# Top.net
KiCad netlist of a schematic drawn in Altium Designer
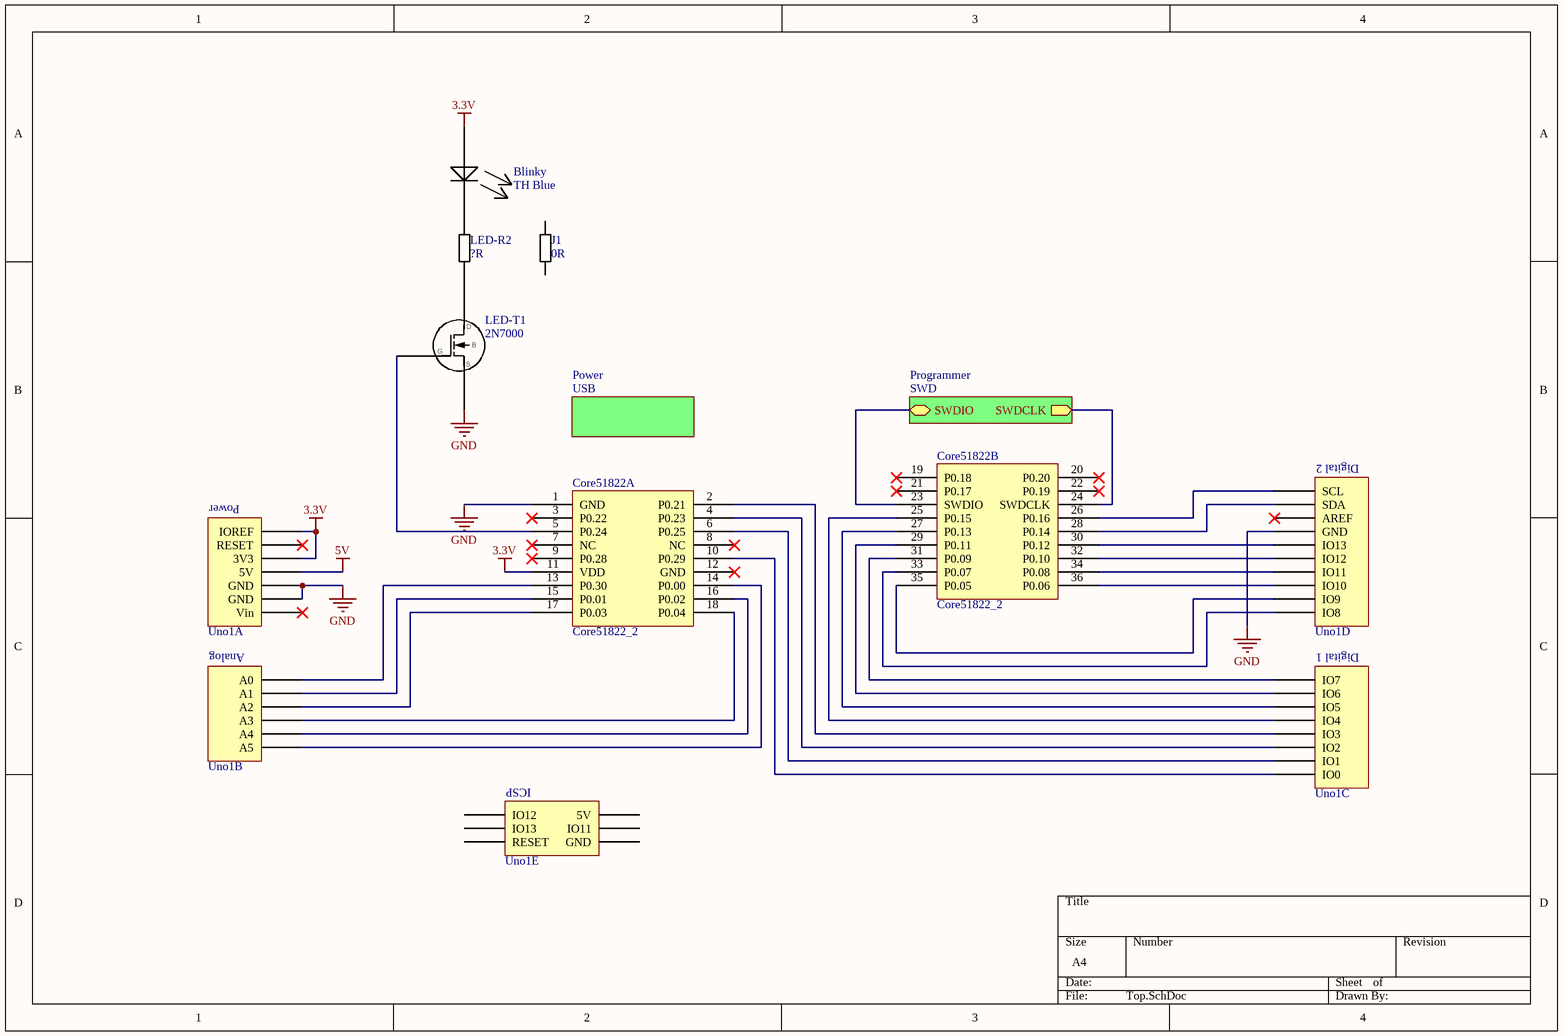
[diagram p0: Top.SchDoc]

(export (version "E")
  (design (tool "Eeschema 10.0.6"))
  (components
    (comp (ref "Blinky") (value "TH Blue") (footprint "LED 3mm") (libsource (lib "LEDs") (part "LED")))
    (comp (ref "Core51822")
      (value "Core51822_2")
      (footprint "Core51822")
      (libsource (lib "Modules") (part "Core51822_2"))
    )
    (comp (ref "J1")
      (value "0R")
      (footprint "R 0805 / 2012 wide")
      (libsource (lib "Standard") (part "Resistor"))
    )
    (comp (ref "LED-R2")
      (value "?R")
      (footprint "R 0805 / 2012")
      (libsource (lib "Standard") (part "Resistor"))
    )
    (comp (ref "LED-T1")
      (value "2N7000")
      (footprint "SOT-23-3")
      (description "N-FET")
      (libsource (lib "ICs") (part "2N7000"))
    )
    (comp (ref "Uno1")
      (value "Arduino Uno")
      (footprint "Arduino Uno Adapter")
      (libsource (lib "Arduino") (part "Arduino Uno"))
    )
  )
  (nets
    (net (code "1") (name "/SWDCLK") (class "Default")
      (node (ref "Core51822") (pin "24") (pinfunction "SWDCLK_24") (pintype "passive"))
    )
    (net (code "2") (name "/SWDIO") (class "Default")
      (node (ref "Core51822") (pin "23") (pinfunction "SWDIO_23") (pintype "passive"))
    )
    (net (code "3") (name "3.3V") (class "Default")
      (node (ref "Blinky") (pin "1") (pinfunction "+_1") (pintype "passive"))
      (node (ref "Core51822") (pin "11") (pinfunction "VDD_11") (pintype "passive"))
      (node (ref "Uno1") (pin "3V3") (pinfunction "3V3_3V3") (pintype "passive"))
      (node (ref "Uno1") (pin "IOREF") (pinfunction "IOREF_IOREF") (pintype "passive"))
    )
    (net (code "4") (name "5V") (class "Default")
      (node (ref "Uno1") (pin "5V") (pinfunction "5V_5V") (pintype "passive"))
    )
    (net (code "5") (name "GND") (class "Default")
      (node (ref "Core51822") (pin "1") (pinfunction "GND_1") (pintype "passive"))
      (node (ref "LED-T1") (pin "2") (pinfunction "2_2") (pintype "passive"))
      (node (ref "Uno1") (pin "GND1") (pinfunction "GND_GND1") (pintype "passive"))
      (node (ref "Uno1") (pin "GND2") (pinfunction "GND_GND2") (pintype "passive"))
      (node (ref "Uno1") (pin "GND3") (pinfunction "GND_GND3") (pintype "passive"))
    )
    (net (code "6") (name "Net-(Blinky--)") (class "Default")
      (node (ref "Blinky") (pin "2") (pinfunction "-_2") (pintype "passive"))
      (node (ref "LED-R2") (pin "2") (pinfunction "2_2") (pintype "passive"))
    )
    (net (code "7") (name "Net-(Core51822A-P0.00)") (class "Default")
      (node (ref "Core51822") (pin "14") (pinfunction "P0.00_14") (pintype "passive"))
      (node (ref "Uno1") (pin "A5") (pinfunction "A5_A5") (pintype "passive"))
    )
    (net (code "8") (name "Net-(Core51822A-P0.01)") (class "Default")
      (node (ref "Core51822") (pin "15") (pinfunction "P0.01_15") (pintype "passive"))
      (node (ref "Uno1") (pin "A1") (pinfunction "A1_A1") (pintype "passive"))
    )
    (net (code "9") (name "Net-(Core51822A-P0.02)") (class "Default")
      (node (ref "Core51822") (pin "16") (pinfunction "P0.02_16") (pintype "passive"))
      (node (ref "Uno1") (pin "A4") (pinfunction "A4_A4") (pintype "passive"))
    )
    (net (code "10") (name "Net-(Core51822A-P0.03)") (class "Default")
      (node (ref "Core51822") (pin "17") (pinfunction "P0.03_17") (pintype "passive"))
      (node (ref "Uno1") (pin "A2") (pinfunction "A2_A2") (pintype "passive"))
    )
    (net (code "11") (name "Net-(Core51822A-P0.04)") (class "Default")
      (node (ref "Core51822") (pin "18") (pinfunction "P0.04_18") (pintype "passive"))
      (node (ref "Uno1") (pin "A3") (pinfunction "A3_A3") (pintype "passive"))
    )
    (net (code "12") (name "Net-(Core51822A-P0.21)") (class "Default")
      (node (ref "Core51822") (pin "2") (pinfunction "P0.21_2") (pintype "passive"))
      (node (ref "Uno1") (pin "3") (pinfunction "IO3_3") (pintype "passive"))
    )
    (net (code "13") (name "Net-(Core51822A-P0.23)") (class "Default")
      (node (ref "Core51822") (pin "4") (pinfunction "P0.23_4") (pintype "passive"))
      (node (ref "Uno1") (pin "2") (pinfunction "IO2_2") (pintype "passive"))
    )
    (net (code "14") (name "Net-(Core51822A-P0.24)") (class "Default")
      (node (ref "Core51822") (pin "5") (pinfunction "P0.24_5") (pintype "passive"))
      (node (ref "LED-T1") (pin "1") (pinfunction "1_1") (pintype "passive"))
    )
    (net (code "15") (name "Net-(Core51822A-P0.25)") (class "Default")
      (node (ref "Core51822") (pin "6") (pinfunction "P0.25_6") (pintype "passive"))
      (node (ref "Uno1") (pin "1") (pinfunction "IO1_1") (pintype "passive"))
    )
    (net (code "16") (name "Net-(Core51822A-P0.29)") (class "Default")
      (node (ref "Core51822") (pin "10") (pinfunction "P0.29_10") (pintype "passive"))
      (node (ref "Uno1") (pin "0") (pinfunction "IO0_0") (pintype "passive"))
    )
    (net (code "17") (name "Net-(Core51822A-P0.30)") (class "Default")
      (node (ref "Core51822") (pin "13") (pinfunction "P0.30_13") (pintype "passive"))
      (node (ref "Uno1") (pin "A0") (pinfunction "A0_A0") (pintype "passive"))
    )
    (net (code "18") (name "Net-(Core51822B-P0.05)") (class "Default")
      (node (ref "Core51822") (pin "35") (pinfunction "P0.05_35") (pintype "passive"))
      (node (ref "Uno1") (pin "9") (pinfunction "IO9_9") (pintype "passive"))
    )
    (net (code "19") (name "Net-(Core51822B-P0.06)") (class "Default")
      (node (ref "Core51822") (pin "36") (pinfunction "P0.06_36") (pintype "passive"))
      (node (ref "Uno1") (pin "10") (pinfunction "IO10_10") (pintype "passive"))
    )
    (net (code "20") (name "Net-(Core51822B-P0.07)") (class "Default")
      (node (ref "Core51822") (pin "33") (pinfunction "P0.07_33") (pintype "passive"))
      (node (ref "Uno1") (pin "8") (pinfunction "IO8_8") (pintype "passive"))
    )
    (net (code "21") (name "Net-(Core51822B-P0.08)") (class "Default")
      (node (ref "Core51822") (pin "34") (pinfunction "P0.08_34") (pintype "passive"))
      (node (ref "Uno1") (pin "11") (pinfunction "IO11_11") (pintype "passive"))
    )
    (net (code "22") (name "Net-(Core51822B-P0.09)") (class "Default")
      (node (ref "Core51822") (pin "31") (pinfunction "P0.09_31") (pintype "passive"))
      (node (ref "Uno1") (pin "7") (pinfunction "IO7_7") (pintype "passive"))
    )
    (net (code "23") (name "Net-(Core51822B-P0.10)") (class "Default")
      (node (ref "Core51822") (pin "32") (pinfunction "P0.10_32") (pintype "passive"))
      (node (ref "Uno1") (pin "12") (pinfunction "IO12_12") (pintype "passive"))
    )
    (net (code "24") (name "Net-(Core51822B-P0.11)") (class "Default")
      (node (ref "Core51822") (pin "29") (pinfunction "P0.11_29") (pintype "passive"))
      (node (ref "Uno1") (pin "6") (pinfunction "IO6_6") (pintype "passive"))
    )
    (net (code "25") (name "Net-(Core51822B-P0.12)") (class "Default")
      (node (ref "Core51822") (pin "30") (pinfunction "P0.12_30") (pintype "passive"))
      (node (ref "Uno1") (pin "13") (pinfunction "IO13_13") (pintype "passive"))
    )
    (net (code "26") (name "Net-(Core51822B-P0.13)") (class "Default")
      (node (ref "Core51822") (pin "27") (pinfunction "P0.13_27") (pintype "passive"))
      (node (ref "Uno1") (pin "5") (pinfunction "IO5_5") (pintype "passive"))
    )
    (net (code "27") (name "Net-(Core51822B-P0.14)") (class "Default")
      (node (ref "Core51822") (pin "28") (pinfunction "P0.14_28") (pintype "passive"))
      (node (ref "Uno1") (pin "SDA") (pinfunction "SDA_SDA") (pintype "passive"))
    )
    (net (code "28") (name "Net-(Core51822B-P0.15)") (class "Default")
      (node (ref "Core51822") (pin "25") (pinfunction "P0.15_25") (pintype "passive"))
      (node (ref "Uno1") (pin "4") (pinfunction "IO4_4") (pintype "passive"))
    )
    (net (code "29") (name "Net-(Core51822B-P0.16)") (class "Default")
      (node (ref "Core51822") (pin "26") (pinfunction "P0.16_26") (pintype "passive"))
      (node (ref "Uno1") (pin "SCL") (pinfunction "SCL_SCL") (pintype "passive"))
    )
    (net (code "30") (name "Net-(LED-R2-Pad1)") (class "Default")
      (node (ref "LED-R2") (pin "1") (pinfunction "1_1") (pintype "passive"))
      (node (ref "LED-T1") (pin "3") (pinfunction "3_3") (pintype "passive"))
    )
    (net (code "31") (name "unconnected-(Core51822A-GND-Pad12)") (class "Default")
      (node (ref "Core51822") (pin "12") (pinfunction "GND_12") (pintype "passive+no_connect"))
    )
    (net (code "32") (name "unconnected-(Core51822A-NC-Pad7)") (class "Default")
      (node (ref "Core51822") (pin "7") (pinfunction "NC_7") (pintype "passive+no_connect"))
    )
    (net (code "33") (name "unconnected-(Core51822A-NC-Pad8)") (class "Default")
      (node (ref "Core51822") (pin "8") (pinfunction "NC_8") (pintype "passive+no_connect"))
    )
    (net (code "34") (name "unconnected-(Core51822A-P0.22-Pad3)") (class "Default")
      (node (ref "Core51822") (pin "3") (pinfunction "P0.22_3") (pintype "passive+no_connect"))
    )
    (net (code "35") (name "unconnected-(Core51822A-P0.28-Pad9)") (class "Default")
      (node (ref "Core51822") (pin "9") (pinfunction "P0.28_9") (pintype "passive+no_connect"))
    )
    (net (code "36") (name "unconnected-(Core51822B-P0.17-Pad21)") (class "Default")
      (node (ref "Core51822") (pin "21") (pinfunction "P0.17_21") (pintype "power_in+no_connect"))
    )
    (net (code "37") (name "unconnected-(Core51822B-P0.18-Pad19)") (class "Default")
      (node (ref "Core51822") (pin "19") (pinfunction "P0.18_19") (pintype "passive+no_connect"))
    )
    (net (code "38") (name "unconnected-(Core51822B-P0.19-Pad22)") (class "Default")
      (node (ref "Core51822") (pin "22") (pinfunction "P0.19_22") (pintype "passive+no_connect"))
    )
    (net (code "39") (name "unconnected-(Core51822B-P0.20-Pad20)") (class "Default")
      (node (ref "Core51822") (pin "20") (pinfunction "P0.20_20") (pintype "passive+no_connect"))
    )
    (net (code "40") (name "unconnected-(J1-Pad1)") (class "Default")
      (node (ref "J1") (pin "1") (pinfunction "1_1") (pintype "passive"))
    )
    (net (code "41") (name "unconnected-(J1-Pad2)") (class "Default")
      (node (ref "J1") (pin "2") (pinfunction "2_2") (pintype "passive"))
    )
    (net (code "42") (name "unconnected-(Uno1-PadAREF)") (class "Default")
      (node (ref "Uno1") (pin "AREF") (pinfunction "AREF_AREF") (pintype "passive+no_connect"))
    )
    (net (code "43") (name "unconnected-(Uno1-PadRESET)") (class "Default")
      (node (ref "Uno1") (pin "RESET") (pinfunction "RESET_RESET") (pintype "passive+no_connect"))
    )
    (net (code "44") (name "unconnected-(Uno1-PadVin)") (class "Default")
      (node (ref "Uno1") (pin "Vin") (pinfunction "Vin_Vin") (pintype "passive+no_connect"))
    )
    (net (code "45") (name "unconnected-(Uno1E-5V-PadICSP2)") (class "Default")
      (node (ref "Uno1") (pin "ICSP2") (pinfunction "5V_ICSP2") (pintype "passive"))
    )
    (net (code "46") (name "unconnected-(Uno1E-GND-PadICSP6)") (class "Default")
      (node (ref "Uno1") (pin "ICSP6") (pinfunction "GND_ICSP6") (pintype "passive"))
    )
    (net (code "47") (name "unconnected-(Uno1E-IO11-PadICSP4)") (class "Default")
      (node (ref "Uno1") (pin "ICSP4") (pinfunction "IO11_ICSP4") (pintype "passive"))
    )
    (net (code "48") (name "unconnected-(Uno1E-IO12-PadICSP1)") (class "Default")
      (node (ref "Uno1") (pin "ICSP1") (pinfunction "IO12_ICSP1") (pintype "passive"))
    )
    (net (code "49") (name "unconnected-(Uno1E-IO13-PadICSP3)") (class "Default")
      (node (ref "Uno1") (pin "ICSP3") (pinfunction "IO13_ICSP3") (pintype "passive"))
    )
    (net (code "50") (name "unconnected-(Uno1E-RESET-PadICSP5)") (class "Default")
      (node (ref "Uno1") (pin "ICSP5") (pinfunction "RESET_ICSP5") (pintype "passive"))
    )
  )
)
